# ProPrj_buatPCB_2026-03-01.net
KiCad netlist of a schematic drawn in EasyEDA Pro
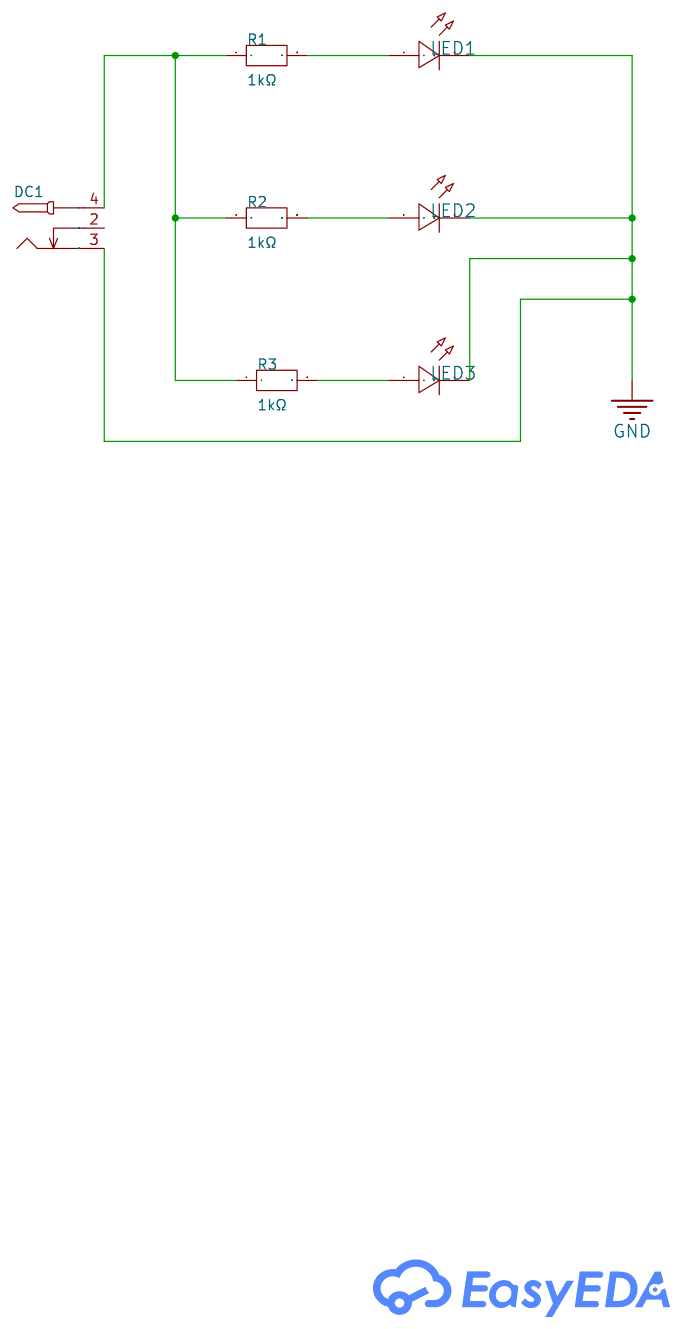
[diagram p0: schematic sheet]

(export (version "E")
  (design (tool "Eeschema 10.0.6"))
  (components
    (comp (ref "DC1")
      (value "~")
      (footprint "easyedapro:DC-IN-TH_DC-5520-1")
      (libsource (lib "easyedapro") (part "DC电源接口"))
    )
    (comp (ref "LED1")
      (value "~")
      (footprint "easyedapro:LED0402-RD_YELLOW")
      (libsource (lib "easyedapro") (part "LED_R"))
    )
    (comp (ref "LED2")
      (value "~")
      (footprint "easyedapro:LED0402-RD_YELLOW")
      (libsource (lib "easyedapro") (part "LED_R"))
    )
    (comp (ref "LED3")
      (value "~")
      (footprint "easyedapro:LED0402-RD_YELLOW")
      (libsource (lib "easyedapro") (part "LED_R"))
    )
    (comp (ref "R1")
      (value "1kΩ")
      (footprint "easyedapro:R0402")
      (fields
        (field (name "Manufacturer Part") "ERJ-PA2D1001X")
        (field (name "Manufacturer") "PANASONIC(松下)")
      )
      (libsource (lib "easyedapro") (part "ERJ-PA2D1001X"))
    )
    (comp (ref "R2")
      (value "1kΩ")
      (footprint "easyedapro:R0402")
      (fields
        (field (name "Manufacturer Part") "ERJ-PA2D1001X")
        (field (name "Manufacturer") "PANASONIC(松下)")
      )
      (libsource (lib "easyedapro") (part "ERJ-PA2D1001X"))
    )
    (comp (ref "R3")
      (value "1kΩ")
      (footprint "easyedapro:R0402")
      (fields
        (field (name "Manufacturer Part") "ERJ-PA2D1001X")
        (field (name "Manufacturer") "PANASONIC(松下)")
      )
      (libsource (lib "easyedapro") (part "ERJ-PA2D1001X"))
    )
  )
  (nets
    (net (code "1") (name "GND") (class "Default")
      (node (ref "DC1") (pin "3") (pinfunction "3_3") (pintype "input"))
      (node (ref "LED1") (pin "2") (pinfunction "C_2") (pintype "input"))
      (node (ref "LED2") (pin "2") (pinfunction "C_2") (pintype "input"))
      (node (ref "LED3") (pin "2") (pinfunction "C_2") (pintype "input"))
    )
    (net (code "2") (name "Net-(DC1-Pad4)") (class "Default")
      (node (ref "DC1") (pin "4") (pinfunction "4_4") (pintype "input"))
      (node (ref "R1") (pin "1") (pinfunction "1_1") (pintype "unspecified"))
      (node (ref "R2") (pin "1") (pinfunction "1_1") (pintype "unspecified"))
      (node (ref "R3") (pin "1") (pinfunction "1_1") (pintype "unspecified"))
    )
    (net (code "3") (name "Net-(LED1-A)") (class "Default")
      (node (ref "LED1") (pin "1") (pinfunction "A_1") (pintype "input"))
      (node (ref "R1") (pin "2") (pinfunction "2_2") (pintype "unspecified"))
    )
    (net (code "4") (name "Net-(LED2-A)") (class "Default")
      (node (ref "LED2") (pin "1") (pinfunction "A_1") (pintype "input"))
      (node (ref "R2") (pin "2") (pinfunction "2_2") (pintype "unspecified"))
    )
    (net (code "5") (name "Net-(LED3-A)") (class "Default")
      (node (ref "LED3") (pin "1") (pinfunction "A_1") (pintype "input"))
      (node (ref "R3") (pin "2") (pinfunction "2_2") (pintype "unspecified"))
    )
    (net (code "6") (name "unconnected-(DC1-Pad2)") (class "Default")
      (node (ref "DC1") (pin "2") (pinfunction "2_2") (pintype "input"))
    )
  )
)
